# ParaquedasV2.net
KiCad netlist of a schematic drawn in EAGLE
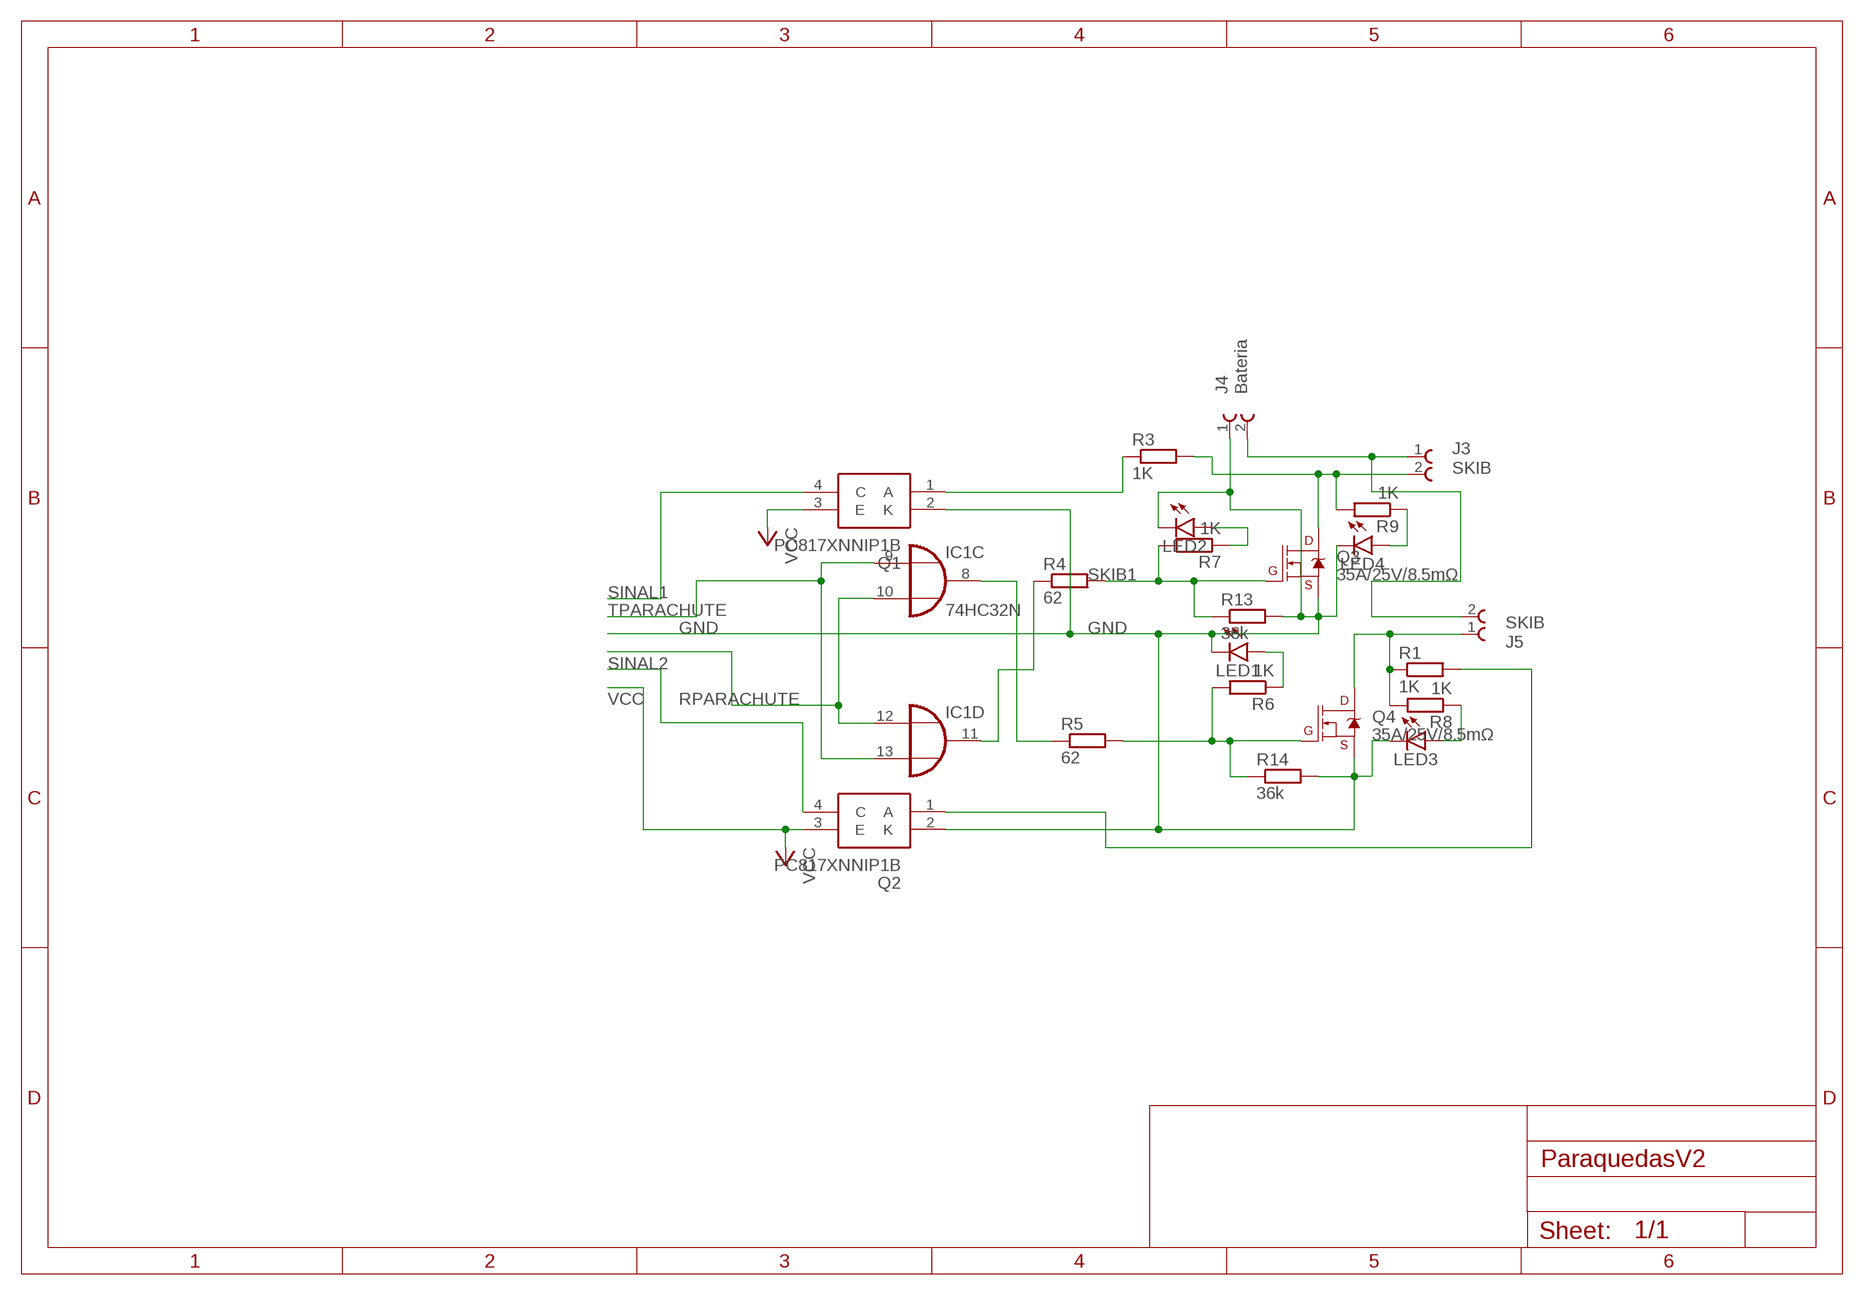
[diagram p0: schematic, sheet 1]

(export (version "E")
  (design (tool "Eeschema 10.0.6"))
  (components
    (comp (ref "IC1")
      (value "74HC32N")
      (footprint "eagle-import:DIL14")
      (libsource (lib "eagle-import") (part "7432NHC"))
    )
    (comp (ref "J3")
      (value "SKIB")
      (footprint "eagle-import:691111710002")
      (fields (field (name "MF") "Wurth Electronics") (field (name "MP") "691111710002"))
      (libsource (lib "eagle-import") (part "691111710002"))
    )
    (comp (ref "J4")
      (value "Bateria")
      (footprint "eagle-import:691111710002")
      (fields (field (name "MF") "Wurth Electronics") (field (name "MP") "691111710002"))
      (libsource (lib "eagle-import") (part "691111710002"))
    )
    (comp (ref "J5")
      (value "SKIB")
      (footprint "eagle-import:691111710002")
      (fields (field (name "MF") "Wurth Electronics") (field (name "MP") "691111710002"))
      (libsource (lib "eagle-import") (part "691111710002"))
    )
    (comp (ref "LED1")
      (value "LEDCHIP-LED0805")
      (footprint "eagle-import:CHIP-LED0805")
      (libsource (lib "eagle-import") (part "LEDCHIP-LED0805"))
    )
    (comp (ref "LED2")
      (value "LEDCHIP-LED0805")
      (footprint "eagle-import:CHIP-LED0805")
      (libsource (lib "eagle-import") (part "LEDCHIP-LED0805"))
    )
    (comp (ref "LED3")
      (value "LEDCHIP-LED0805")
      (footprint "eagle-import:CHIP-LED0805")
      (libsource (lib "eagle-import") (part "LEDCHIP-LED0805"))
    )
    (comp (ref "LED4")
      (value "LEDCHIP-LED0805")
      (footprint "eagle-import:CHIP-LED0805")
      (libsource (lib "eagle-import") (part "LEDCHIP-LED0805"))
    )
    (comp (ref "Q1")
      (value "PC817XNNIP1B")
      (footprint "eagle-import:SOP254P960X420-4N")
      (fields (field (name "MOUSER_PART_NUMBER") "852-PC817XNNIP1B"))
      (libsource (lib "eagle-import") (part "PC817XNNIP1B"))
    )
    (comp (ref "Q2")
      (value "PC817XNNIP1B")
      (footprint "eagle-import:SOP254P960X420-4N")
      (fields (field (name "MOUSER_PART_NUMBER") "852-PC817XNNIP1B"))
      (libsource (lib "eagle-import") (part "PC817XNNIP1B"))
    )
    (comp (ref "Q3")
      (value "35A/25V/8.5mΩ")
      (footprint "eagle-import:TO-252_DPAK")
      (libsource (lib "eagle-import") (part "MOSFET-NCH-FDD8780"))
    )
    (comp (ref "Q4")
      (value "35A/25V/8.5mΩ")
      (footprint "eagle-import:TO-252_DPAK")
      (libsource (lib "eagle-import") (part "MOSFET-NCH-FDD8780"))
    )
    (comp (ref "R1")
      (value "1K")
      (footprint "eagle-import:R0603")
      (libsource (lib "eagle-import") (part "R-EU_R0603"))
    )
    (comp (ref "R3")
      (value "1K")
      (footprint "eagle-import:R0603")
      (libsource (lib "eagle-import") (part "R-EU_R0603"))
    )
    (comp (ref "R4")
      (value "62")
      (footprint "eagle-import:M0805")
      (libsource (lib "eagle-import") (part "R-EU_M0805"))
    )
    (comp (ref "R5")
      (value "62")
      (footprint "eagle-import:M0805")
      (libsource (lib "eagle-import") (part "R-EU_M0805"))
    )
    (comp (ref "R6")
      (value "1K")
      (footprint "eagle-import:M0805")
      (libsource (lib "eagle-import") (part "R-EU_M0805"))
    )
    (comp (ref "R7")
      (value "1K")
      (footprint "eagle-import:M0805")
      (libsource (lib "eagle-import") (part "R-EU_M0805"))
    )
    (comp (ref "R8")
      (value "1K")
      (footprint "eagle-import:M0805")
      (libsource (lib "eagle-import") (part "R-EU_M0805"))
    )
    (comp (ref "R9")
      (value "1K")
      (footprint "eagle-import:M0805")
      (libsource (lib "eagle-import") (part "R-EU_M0805"))
    )
    (comp (ref "R13")
      (value "36k")
      (footprint "eagle-import:M0805")
      (libsource (lib "eagle-import") (part "R-EU_M0805"))
    )
    (comp (ref "R14")
      (value "36k")
      (footprint "eagle-import:M0805")
      (libsource (lib "eagle-import") (part "R-EU_M0805"))
    )
  )
  (nets
    (net (code "1") (name "/GND") (class "Default")
      (node (ref "J4") (pin "1") (pinfunction "1_1") (pintype "passive"))
      (node (ref "LED1") (pin "C") (pinfunction "C_C") (pintype "passive"))
      (node (ref "LED2") (pin "C") (pinfunction "C_C") (pintype "passive"))
      (node (ref "LED3") (pin "C") (pinfunction "C_C") (pintype "passive"))
      (node (ref "LED4") (pin "C") (pinfunction "C_C") (pintype "passive"))
      (node (ref "Q1") (pin "2") (pinfunction "K_2") (pintype "bidirectional"))
      (node (ref "Q2") (pin "2") (pinfunction "K_2") (pintype "bidirectional"))
      (node (ref "Q3") (pin "3") (pinfunction "S_3") (pintype "bidirectional"))
      (node (ref "Q4") (pin "3") (pinfunction "S_3") (pintype "bidirectional"))
      (node (ref "R13") (pin "2") (pinfunction "2_2") (pintype "passive"))
      (node (ref "R14") (pin "2") (pinfunction "2_2") (pintype "passive"))
    )
    (net (code "2") (name "/RPARACHUTE") (class "Default")
      (node (ref "IC1") (pin "10") (pinfunction "I1_10") (pintype "input"))
      (node (ref "IC1") (pin "12") (pinfunction "I0_12") (pintype "input"))
    )
    (net (code "3") (name "/SINAL1") (class "Default")
      (node (ref "Q1") (pin "4") (pinfunction "C_4") (pintype "bidirectional"))
    )
    (net (code "4") (name "/SINAL2") (class "Default")
      (node (ref "Q2") (pin "4") (pinfunction "C_4") (pintype "bidirectional"))
    )
    (net (code "5") (name "/SKIB1") (class "Default")
      (node (ref "Q3") (pin "1") (pinfunction "G_1") (pintype "bidirectional"))
      (node (ref "R13") (pin "1") (pinfunction "1_1") (pintype "passive"))
      (node (ref "R4") (pin "2") (pinfunction "2_2") (pintype "passive"))
      (node (ref "R7") (pin "2") (pinfunction "2_2") (pintype "passive"))
    )
    (net (code "6") (name "/TPARACHUTE") (class "Default")
      (node (ref "IC1") (pin "13") (pinfunction "I1_13") (pintype "input"))
      (node (ref "IC1") (pin "9") (pinfunction "I0_9") (pintype "input"))
    )
    (net (code "7") (name "Net-(IC1C-O)") (class "Default")
      (node (ref "IC1") (pin "8") (pinfunction "O_8") (pintype "output"))
      (node (ref "R5") (pin "1") (pinfunction "1_1") (pintype "passive"))
    )
    (net (code "8") (name "Net-(IC1D-O)") (class "Default")
      (node (ref "IC1") (pin "11") (pinfunction "O_11") (pintype "output"))
      (node (ref "R4") (pin "1") (pinfunction "1_1") (pintype "passive"))
    )
    (net (code "9") (name "Net-(J3-Pad1)") (class "Default")
      (node (ref "J3") (pin "1") (pinfunction "1_1") (pintype "passive"))
      (node (ref "J4") (pin "2") (pinfunction "2_2") (pintype "passive"))
      (node (ref "J5") (pin "2") (pinfunction "2_2") (pintype "passive"))
    )
    (net (code "10") (name "Net-(LED1-PadA)") (class "Default")
      (node (ref "LED1") (pin "A") (pinfunction "A_A") (pintype "passive"))
      (node (ref "R6") (pin "1") (pinfunction "1_1") (pintype "passive"))
    )
    (net (code "11") (name "Net-(LED2-PadA)") (class "Default")
      (node (ref "LED2") (pin "A") (pinfunction "A_A") (pintype "passive"))
      (node (ref "R7") (pin "1") (pinfunction "1_1") (pintype "passive"))
    )
    (net (code "12") (name "Net-(LED3-PadA)") (class "Default")
      (node (ref "LED3") (pin "A") (pinfunction "A_A") (pintype "passive"))
      (node (ref "R8") (pin "1") (pinfunction "1_1") (pintype "passive"))
    )
    (net (code "13") (name "Net-(LED4-PadA)") (class "Default")
      (node (ref "LED4") (pin "A") (pinfunction "A_A") (pintype "passive"))
      (node (ref "R9") (pin "1") (pinfunction "1_1") (pintype "passive"))
    )
    (net (code "14") (name "Net-(Q1-A)") (class "Default")
      (node (ref "Q1") (pin "1") (pinfunction "A_1") (pintype "bidirectional"))
      (node (ref "R3") (pin "1") (pinfunction "1_1") (pintype "passive"))
    )
    (net (code "15") (name "Net-(Q2-A)") (class "Default")
      (node (ref "Q2") (pin "1") (pinfunction "A_1") (pintype "bidirectional"))
      (node (ref "R1") (pin "2") (pinfunction "2_2") (pintype "passive"))
    )
    (net (code "16") (name "Net-(Q3-D)") (class "Default")
      (node (ref "J3") (pin "2") (pinfunction "2_2") (pintype "passive"))
      (node (ref "Q3") (pin "2") (pinfunction "D_2") (pintype "bidirectional"))
      (node (ref "R3") (pin "2") (pinfunction "2_2") (pintype "passive"))
      (node (ref "R9") (pin "2") (pinfunction "2_2") (pintype "passive"))
    )
    (net (code "17") (name "Net-(Q4-D)") (class "Default")
      (node (ref "J5") (pin "1") (pinfunction "1_1") (pintype "passive"))
      (node (ref "Q4") (pin "2") (pinfunction "D_2") (pintype "bidirectional"))
      (node (ref "R1") (pin "1") (pinfunction "1_1") (pintype "passive"))
      (node (ref "R8") (pin "2") (pinfunction "2_2") (pintype "passive"))
    )
    (net (code "18") (name "Net-(Q4-G)") (class "Default")
      (node (ref "Q4") (pin "1") (pinfunction "G_1") (pintype "bidirectional"))
      (node (ref "R14") (pin "1") (pinfunction "1_1") (pintype "passive"))
      (node (ref "R5") (pin "2") (pinfunction "2_2") (pintype "passive"))
      (node (ref "R6") (pin "2") (pinfunction "2_2") (pintype "passive"))
    )
    (net (code "19") (name "VCC") (class "Default")
      (node (ref "Q1") (pin "3") (pinfunction "E_3") (pintype "bidirectional"))
      (node (ref "Q2") (pin "3") (pinfunction "E_3") (pintype "bidirectional"))
    )
  )
)
